# dynalo.net
KiCad netlist of a schematic drawn in EAGLE
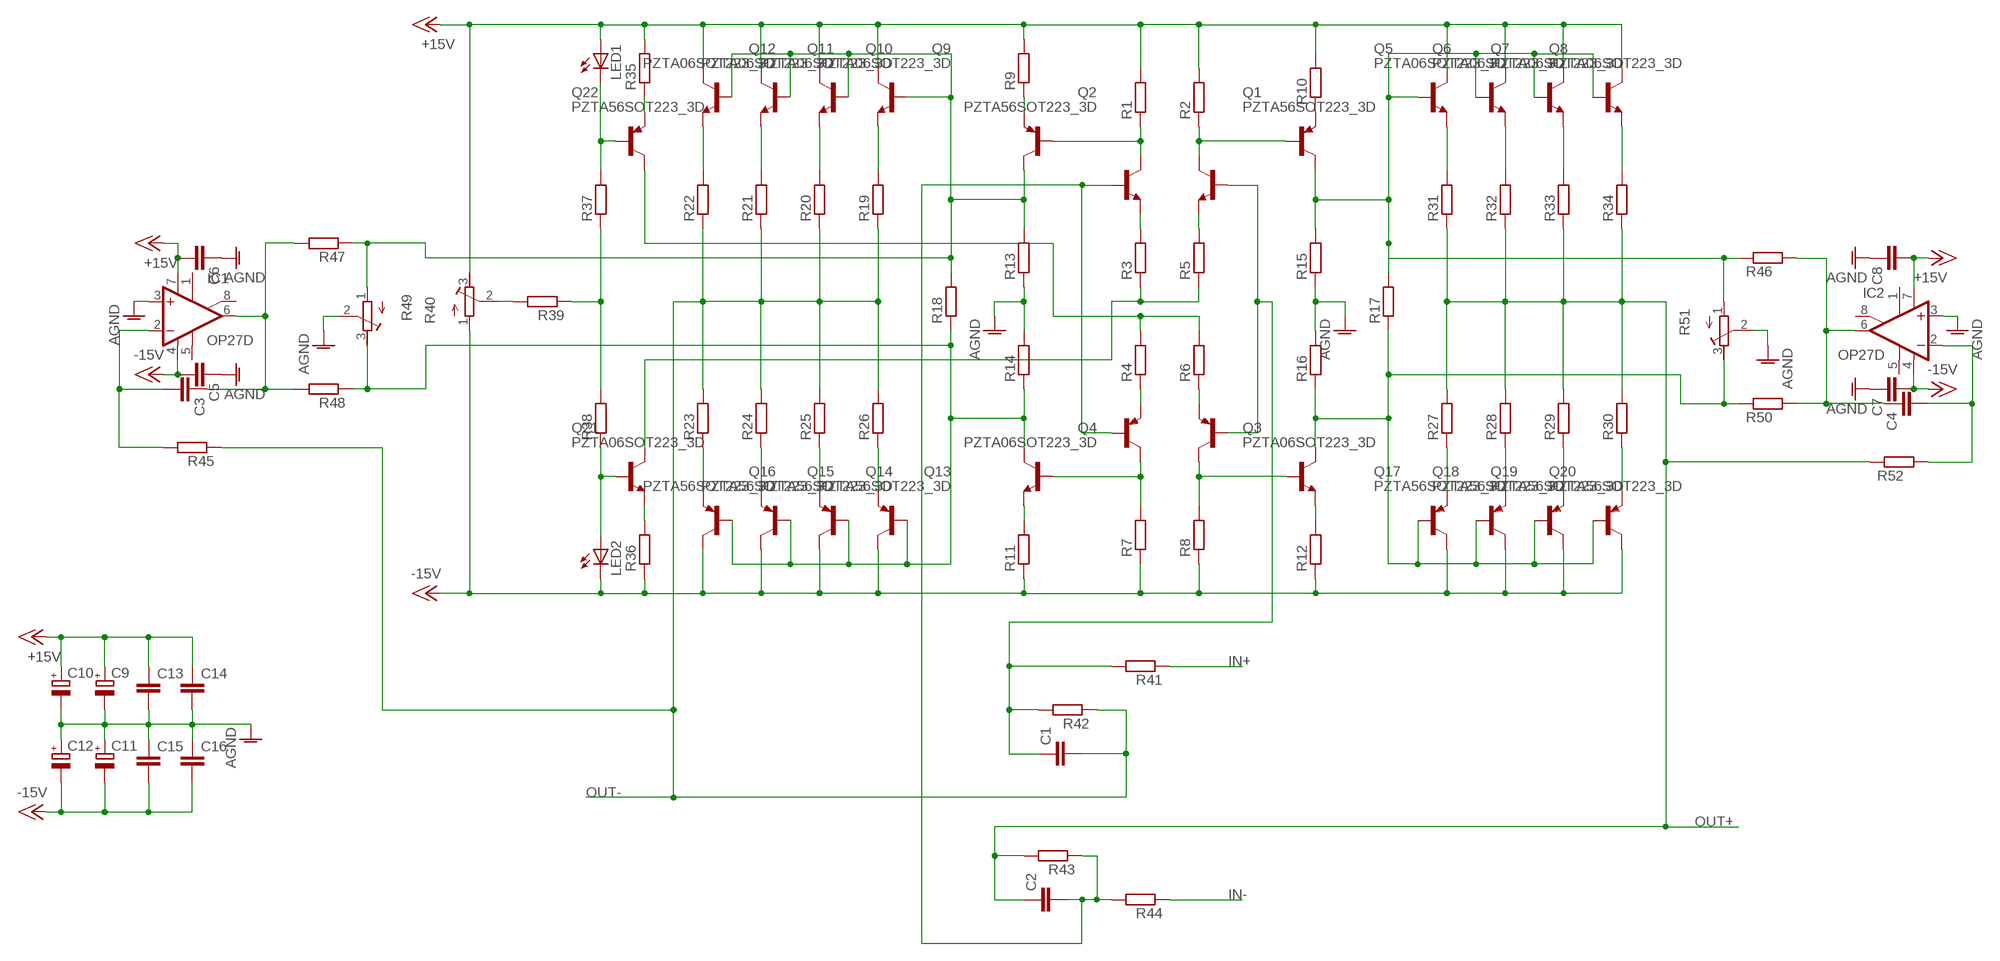
[diagram p0: schematic, sheet 1]

(export (version "E")
  (design (tool "Eeschema 10.0.6"))
  (components
    (comp (ref "C1")
      (value "C-EUC0805K")
      (footprint "eagle-import:C0805K")
      (libsource (lib "eagle-import") (part "C-EUC0805K"))
    )
    (comp (ref "C2")
      (value "C-EUC0805K")
      (footprint "eagle-import:C0805K")
      (libsource (lib "eagle-import") (part "C-EUC0805K"))
    )
    (comp (ref "C3")
      (value "C-EUC0805K")
      (footprint "eagle-import:C0805K")
      (libsource (lib "eagle-import") (part "C-EUC0805K"))
    )
    (comp (ref "C4")
      (value "C-EUC0805K")
      (footprint "eagle-import:C0805K")
      (libsource (lib "eagle-import") (part "C-EUC0805K"))
    )
    (comp (ref "C5")
      (value "C-EUC0805K")
      (footprint "eagle-import:C0805K")
      (libsource (lib "eagle-import") (part "C-EUC0805K"))
    )
    (comp (ref "C6")
      (value "C-EUC0805K")
      (footprint "eagle-import:C0805K")
      (libsource (lib "eagle-import") (part "C-EUC0805K"))
    )
    (comp (ref "C7")
      (value "C-EUC0805K")
      (footprint "eagle-import:C0805K")
      (libsource (lib "eagle-import") (part "C-EUC0805K"))
    )
    (comp (ref "C8")
      (value "C-EUC0805K")
      (footprint "eagle-import:C0805K")
      (libsource (lib "eagle-import") (part "C-EUC0805K"))
    )
    (comp (ref "C9")
      (value "CPOL-EUE5-10.5")
      (footprint "eagle-import:E5-10,5")
      (libsource (lib "eagle-import") (part "CPOL-EUE5-10.5"))
    )
    (comp (ref "C10")
      (value "CPOL-EUE5-10.5")
      (footprint "eagle-import:E5-10,5")
      (libsource (lib "eagle-import") (part "CPOL-EUE5-10.5"))
    )
    (comp (ref "C11")
      (value "CPOL-EUE5-10.5")
      (footprint "eagle-import:E5-10,5")
      (libsource (lib "eagle-import") (part "CPOL-EUE5-10.5"))
    )
    (comp (ref "C12")
      (value "CPOL-EUE5-10.5")
      (footprint "eagle-import:E5-10,5")
      (libsource (lib "eagle-import") (part "CPOL-EUE5-10.5"))
    )
    (comp (ref "C13")
      (value "C-EU050-035X075")
      (footprint "eagle-import:C050-035X075")
      (libsource (lib "eagle-import") (part "C-EU050-035X075"))
    )
    (comp (ref "C14")
      (value "C-EU050-035X075")
      (footprint "eagle-import:C050-035X075")
      (libsource (lib "eagle-import") (part "C-EU050-035X075"))
    )
    (comp (ref "C15")
      (value "C-EU050-035X075")
      (footprint "eagle-import:C050-035X075")
      (libsource (lib "eagle-import") (part "C-EU050-035X075"))
    )
    (comp (ref "C16")
      (value "C-EU050-035X075")
      (footprint "eagle-import:C050-035X075")
      (libsource (lib "eagle-import") (part "C-EU050-035X075"))
    )
    (comp (ref "IC1")
      (value "OP27D")
      (footprint "eagle-import:SO08")
      (libsource (lib "eagle-import") (part "OP27D"))
    )
    (comp (ref "IC2")
      (value "OP27D")
      (footprint "eagle-import:SO08")
      (libsource (lib "eagle-import") (part "OP27D"))
    )
    (comp (ref "LED1")
      (value "LED5MM")
      (footprint "eagle-import:LED5MM")
      (libsource (lib "eagle-import") (part "LED5MM"))
    )
    (comp (ref "LED2")
      (value "LED5MM")
      (footprint "eagle-import:LED5MM")
      (libsource (lib "eagle-import") (part "LED5MM"))
    )
    (comp (ref "Q1")
      (value "PZTA56SOT223_3D")
      (footprint "eagle-import:SOT230P700X180-4")
      (libsource (lib "eagle-import") (part "PZTA56SOT223_3D"))
    )
    (comp (ref "Q2")
      (value "PZTA56SOT223_3D")
      (footprint "eagle-import:SOT230P700X180-4")
      (libsource (lib "eagle-import") (part "PZTA56SOT223_3D"))
    )
    (comp (ref "Q3")
      (value "PZTA06SOT223_3D")
      (footprint "eagle-import:SOT230P700X180-4")
      (libsource (lib "eagle-import") (part "PZTA06SOT223_3D"))
    )
    (comp (ref "Q4")
      (value "PZTA06SOT223_3D")
      (footprint "eagle-import:SOT230P700X180-4")
      (libsource (lib "eagle-import") (part "PZTA06SOT223_3D"))
    )
    (comp (ref "Q5")
      (value "PZTA06SOT223_3D")
      (footprint "eagle-import:SOT230P700X180-4")
      (libsource (lib "eagle-import") (part "PZTA06SOT223_3D"))
    )
    (comp (ref "Q6")
      (value "PZTA06SOT223_3D")
      (footprint "eagle-import:SOT230P700X180-4")
      (libsource (lib "eagle-import") (part "PZTA06SOT223_3D"))
    )
    (comp (ref "Q7")
      (value "PZTA06SOT223_3D")
      (footprint "eagle-import:SOT230P700X180-4")
      (libsource (lib "eagle-import") (part "PZTA06SOT223_3D"))
    )
    (comp (ref "Q8")
      (value "PZTA06SOT223_3D")
      (footprint "eagle-import:SOT230P700X180-4")
      (libsource (lib "eagle-import") (part "PZTA06SOT223_3D"))
    )
    (comp (ref "Q9")
      (value "PZTA06SOT223_3D")
      (footprint "eagle-import:SOT230P700X180-4")
      (libsource (lib "eagle-import") (part "PZTA06SOT223_3D"))
    )
    (comp (ref "Q10")
      (value "PZTA06SOT223_3D")
      (footprint "eagle-import:SOT230P700X180-4")
      (libsource (lib "eagle-import") (part "PZTA06SOT223_3D"))
    )
    (comp (ref "Q11")
      (value "PZTA06SOT223_3D")
      (footprint "eagle-import:SOT230P700X180-4")
      (libsource (lib "eagle-import") (part "PZTA06SOT223_3D"))
    )
    (comp (ref "Q12")
      (value "PZTA06SOT223_3D")
      (footprint "eagle-import:SOT230P700X180-4")
      (libsource (lib "eagle-import") (part "PZTA06SOT223_3D"))
    )
    (comp (ref "Q13")
      (value "PZTA56SOT223_3D")
      (footprint "eagle-import:SOT230P700X180-4")
      (libsource (lib "eagle-import") (part "PZTA56SOT223_3D"))
    )
    (comp (ref "Q14")
      (value "PZTA56SOT223_3D")
      (footprint "eagle-import:SOT230P700X180-4")
      (libsource (lib "eagle-import") (part "PZTA56SOT223_3D"))
    )
    (comp (ref "Q15")
      (value "PZTA56SOT223_3D")
      (footprint "eagle-import:SOT230P700X180-4")
      (libsource (lib "eagle-import") (part "PZTA56SOT223_3D"))
    )
    (comp (ref "Q16")
      (value "PZTA56SOT223_3D")
      (footprint "eagle-import:SOT230P700X180-4")
      (libsource (lib "eagle-import") (part "PZTA56SOT223_3D"))
    )
    (comp (ref "Q17")
      (value "PZTA56SOT223_3D")
      (footprint "eagle-import:SOT230P700X180-4")
      (libsource (lib "eagle-import") (part "PZTA56SOT223_3D"))
    )
    (comp (ref "Q18")
      (value "PZTA56SOT223_3D")
      (footprint "eagle-import:SOT230P700X180-4")
      (libsource (lib "eagle-import") (part "PZTA56SOT223_3D"))
    )
    (comp (ref "Q19")
      (value "PZTA56SOT223_3D")
      (footprint "eagle-import:SOT230P700X180-4")
      (libsource (lib "eagle-import") (part "PZTA56SOT223_3D"))
    )
    (comp (ref "Q20")
      (value "PZTA56SOT223_3D")
      (footprint "eagle-import:SOT230P700X180-4")
      (libsource (lib "eagle-import") (part "PZTA56SOT223_3D"))
    )
    (comp (ref "Q21")
      (value "PZTA06SOT223_3D")
      (footprint "eagle-import:SOT230P700X180-4")
      (libsource (lib "eagle-import") (part "PZTA06SOT223_3D"))
    )
    (comp (ref "Q22")
      (value "PZTA56SOT223_3D")
      (footprint "eagle-import:SOT230P700X180-4")
      (libsource (lib "eagle-import") (part "PZTA56SOT223_3D"))
    )
    (comp (ref "R1")
      (value "R-EU_MMA0204")
      (footprint "eagle-import:RESMELF3413")
      (libsource (lib "eagle-import") (part "R-EU_MMA0204"))
    )
    (comp (ref "R2")
      (value "R-EU_MMA0204")
      (footprint "eagle-import:RESMELF3413")
      (libsource (lib "eagle-import") (part "R-EU_MMA0204"))
    )
    (comp (ref "R3")
      (value "R-EU_MMA0204")
      (footprint "eagle-import:RESMELF3413")
      (libsource (lib "eagle-import") (part "R-EU_MMA0204"))
    )
    (comp (ref "R4")
      (value "R-EU_MMA0204")
      (footprint "eagle-import:RESMELF3413")
      (libsource (lib "eagle-import") (part "R-EU_MMA0204"))
    )
    (comp (ref "R5")
      (value "R-EU_MMA0204")
      (footprint "eagle-import:RESMELF3413")
      (libsource (lib "eagle-import") (part "R-EU_MMA0204"))
    )
    (comp (ref "R6")
      (value "R-EU_MMA0204")
      (footprint "eagle-import:RESMELF3413")
      (libsource (lib "eagle-import") (part "R-EU_MMA0204"))
    )
    (comp (ref "R7")
      (value "R-EU_MMA0204")
      (footprint "eagle-import:RESMELF3413")
      (libsource (lib "eagle-import") (part "R-EU_MMA0204"))
    )
    (comp (ref "R8")
      (value "R-EU_MMA0204")
      (footprint "eagle-import:RESMELF3413")
      (libsource (lib "eagle-import") (part "R-EU_MMA0204"))
    )
    (comp (ref "R9")
      (value "R-EU_MMA0204")
      (footprint "eagle-import:RESMELF3413")
      (libsource (lib "eagle-import") (part "R-EU_MMA0204"))
    )
    (comp (ref "R10")
      (value "R-EU_MMA0204")
      (footprint "eagle-import:RESMELF3413")
      (libsource (lib "eagle-import") (part "R-EU_MMA0204"))
    )
    (comp (ref "R11")
      (value "R-EU_MMA0204")
      (footprint "eagle-import:RESMELF3413")
      (libsource (lib "eagle-import") (part "R-EU_MMA0204"))
    )
    (comp (ref "R12")
      (value "R-EU_MMA0204")
      (footprint "eagle-import:RESMELF3413")
      (libsource (lib "eagle-import") (part "R-EU_MMA0204"))
    )
    (comp (ref "R13")
      (value "R-EU_MMA0204")
      (footprint "eagle-import:RESMELF3413")
      (libsource (lib "eagle-import") (part "R-EU_MMA0204"))
    )
    (comp (ref "R14")
      (value "R-EU_MMA0204")
      (footprint "eagle-import:RESMELF3413")
      (libsource (lib "eagle-import") (part "R-EU_MMA0204"))
    )
    (comp (ref "R15")
      (value "R-EU_MMA0204")
      (footprint "eagle-import:RESMELF3413")
      (libsource (lib "eagle-import") (part "R-EU_MMA0204"))
    )
    (comp (ref "R16")
      (value "R-EU_MMA0204")
      (footprint "eagle-import:RESMELF3413")
      (libsource (lib "eagle-import") (part "R-EU_MMA0204"))
    )
    (comp (ref "R17")
      (value "R-EU_MMA0204")
      (footprint "eagle-import:RESMELF3413")
      (libsource (lib "eagle-import") (part "R-EU_MMA0204"))
    )
    (comp (ref "R18")
      (value "R-EU_MMA0204")
      (footprint "eagle-import:RESMELF3413")
      (libsource (lib "eagle-import") (part "R-EU_MMA0204"))
    )
    (comp (ref "R19")
      (value "R-EU_MMA0204")
      (footprint "eagle-import:RESMELF3413")
      (libsource (lib "eagle-import") (part "R-EU_MMA0204"))
    )
    (comp (ref "R20")
      (value "R-EU_MMA0204")
      (footprint "eagle-import:RESMELF3413")
      (libsource (lib "eagle-import") (part "R-EU_MMA0204"))
    )
    (comp (ref "R21")
      (value "R-EU_MMA0204")
      (footprint "eagle-import:RESMELF3413")
      (libsource (lib "eagle-import") (part "R-EU_MMA0204"))
    )
    (comp (ref "R22")
      (value "R-EU_MMA0204")
      (footprint "eagle-import:RESMELF3413")
      (libsource (lib "eagle-import") (part "R-EU_MMA0204"))
    )
    (comp (ref "R23")
      (value "R-EU_MMA0204")
      (footprint "eagle-import:RESMELF3413")
      (libsource (lib "eagle-import") (part "R-EU_MMA0204"))
    )
    (comp (ref "R24")
      (value "R-EU_MMA0204")
      (footprint "eagle-import:RESMELF3413")
      (libsource (lib "eagle-import") (part "R-EU_MMA0204"))
    )
    (comp (ref "R25")
      (value "R-EU_MMA0204")
      (footprint "eagle-import:RESMELF3413")
      (libsource (lib "eagle-import") (part "R-EU_MMA0204"))
    )
    (comp (ref "R26")
      (value "R-EU_MMA0204")
      (footprint "eagle-import:RESMELF3413")
      (libsource (lib "eagle-import") (part "R-EU_MMA0204"))
    )
    (comp (ref "R27")
      (value "R-EU_MMA0204")
      (footprint "eagle-import:RESMELF3413")
      (libsource (lib "eagle-import") (part "R-EU_MMA0204"))
    )
    (comp (ref "R28")
      (value "R-EU_MMA0204")
      (footprint "eagle-import:RESMELF3413")
      (libsource (lib "eagle-import") (part "R-EU_MMA0204"))
    )
    (comp (ref "R29")
      (value "R-EU_MMA0204")
      (footprint "eagle-import:RESMELF3413")
      (libsource (lib "eagle-import") (part "R-EU_MMA0204"))
    )
    (comp (ref "R30")
      (value "R-EU_MMA0204")
      (footprint "eagle-import:RESMELF3413")
      (libsource (lib "eagle-import") (part "R-EU_MMA0204"))
    )
    (comp (ref "R31")
      (value "R-EU_MMA0204")
      (footprint "eagle-import:RESMELF3413")
      (libsource (lib "eagle-import") (part "R-EU_MMA0204"))
    )
    (comp (ref "R32")
      (value "R-EU_MMA0204")
      (footprint "eagle-import:RESMELF3413")
      (libsource (lib "eagle-import") (part "R-EU_MMA0204"))
    )
    (comp (ref "R33")
      (value "R-EU_MMA0204")
      (footprint "eagle-import:RESMELF3413")
      (libsource (lib "eagle-import") (part "R-EU_MMA0204"))
    )
    (comp (ref "R34")
      (value "R-EU_MMA0204")
      (footprint "eagle-import:RESMELF3413")
      (libsource (lib "eagle-import") (part "R-EU_MMA0204"))
    )
    (comp (ref "R35")
      (value "R-EU_MMA0204")
      (footprint "eagle-import:RESMELF3413")
      (libsource (lib "eagle-import") (part "R-EU_MMA0204"))
    )
    (comp (ref "R36")
      (value "R-EU_MMA0204")
      (footprint "eagle-import:RESMELF3413")
      (libsource (lib "eagle-import") (part "R-EU_MMA0204"))
    )
    (comp (ref "R37")
      (value "R-EU_MMA0204")
      (footprint "eagle-import:RESMELF3413")
      (libsource (lib "eagle-import") (part "R-EU_MMA0204"))
    )
    (comp (ref "R38")
      (value "R-EU_MMA0204")
      (footprint "eagle-import:RESMELF3413")
      (libsource (lib "eagle-import") (part "R-EU_MMA0204"))
    )
    (comp (ref "R39")
      (value "R-EU_MELF0204W")
      (footprint "eagle-import:MINI_MELF-0204W")
      (libsource (lib "eagle-import") (part "R-EU_MELF0204W"))
    )
    (comp (ref "R40")
      (value "R-TRIMM3296W")
      (footprint "eagle-import:RTRIM3296W")
      (libsource (lib "eagle-import") (part "R-TRIMM3296W"))
    )
    (comp (ref "R41")
      (value "R-EU_MMA0204")
      (footprint "eagle-import:RESMELF3413")
      (libsource (lib "eagle-import") (part "R-EU_MMA0204"))
    )
    (comp (ref "R42")
      (value "R-EU_MMA0204")
      (footprint "eagle-import:RESMELF3413")
      (libsource (lib "eagle-import") (part "R-EU_MMA0204"))
    )
    (comp (ref "R43")
      (value "R-EU_MMA0204")
      (footprint "eagle-import:RESMELF3413")
      (libsource (lib "eagle-import") (part "R-EU_MMA0204"))
    )
    (comp (ref "R44")
      (value "R-EU_MMA0204")
      (footprint "eagle-import:RESMELF3413")
      (libsource (lib "eagle-import") (part "R-EU_MMA0204"))
    )
    (comp (ref "R45")
      (value "R-EU_MMA0204")
      (footprint "eagle-import:RESMELF3413")
      (libsource (lib "eagle-import") (part "R-EU_MMA0204"))
    )
    (comp (ref "R46")
      (value "R-EU_MMA0204")
      (footprint "eagle-import:RESMELF3413")
      (libsource (lib "eagle-import") (part "R-EU_MMA0204"))
    )
    (comp (ref "R47")
      (value "R-EU_MMA0204")
      (footprint "eagle-import:RESMELF3413")
      (libsource (lib "eagle-import") (part "R-EU_MMA0204"))
    )
    (comp (ref "R48")
      (value "R-EU_MMA0204")
      (footprint "eagle-import:RESMELF3413")
      (libsource (lib "eagle-import") (part "R-EU_MMA0204"))
    )
    (comp (ref "R49")
      (value "R-TRIMM3296W")
      (footprint "eagle-import:RTRIM3296W")
      (libsource (lib "eagle-import") (part "R-TRIMM3296W"))
    )
    (comp (ref "R50")
      (value "R-EU_MMA0204")
      (footprint "eagle-import:RESMELF3413")
      (libsource (lib "eagle-import") (part "R-EU_MMA0204"))
    )
    (comp (ref "R51")
      (value "R-TRIMM3296W")
      (footprint "eagle-import:RTRIM3296W")
      (libsource (lib "eagle-import") (part "R-TRIMM3296W"))
    )
    (comp (ref "R52")
      (value "R-EU_MMA0204")
      (footprint "eagle-import:RESMELF3413")
      (libsource (lib "eagle-import") (part "R-EU_MMA0204"))
    )
    (comp (ref "U$1")
      (value "TRANSISTOR-ARRAYS_THAT340THAT3403D")
      (footprint "eagle-import:DIP762W53P254L1969H508Q14A")
      (libsource (lib "eagle-import") (part "TRANSISTOR-ARRAYS_THAT340THAT3403D"))
    )
  )
  (nets
    (net (code "1") (name "+15V") (class "Default")
      (node (ref "C10") (pin "+") (pinfunction "+_+") (pintype "passive"))
      (node (ref "C13") (pin "1") (pinfunction "1_1") (pintype "passive"))
      (node (ref "C14") (pin "1") (pinfunction "1_1") (pintype "passive"))
      (node (ref "C6") (pin "2") (pinfunction "2_2") (pintype "passive"))
      (node (ref "C8") (pin "2") (pinfunction "2_2") (pintype "passive"))
      (node (ref "C9") (pin "+") (pinfunction "+_+") (pintype "passive"))
      (node (ref "IC1") (pin "7") (pinfunction "V+_7") (pintype "power_in"))
      (node (ref "IC2") (pin "7") (pinfunction "V+_7") (pintype "power_in"))
      (node (ref "LED1") (pin "A") (pinfunction "A_A") (pintype "passive"))
      (node (ref "Q10") (pin "2") (pinfunction "C_2") (pintype "passive"))
      (node (ref "Q10") (pin "4") (pinfunction "C_4") (pintype "passive"))
      (node (ref "Q11") (pin "2") (pinfunction "C_2") (pintype "passive"))
      (node (ref "Q11") (pin "4") (pinfunction "C_4") (pintype "passive"))
      (node (ref "Q12") (pin "2") (pinfunction "C_2") (pintype "passive"))
      (node (ref "Q12") (pin "4") (pinfunction "C_4") (pintype "passive"))
      (node (ref "Q5") (pin "2") (pinfunction "C_2") (pintype "passive"))
      (node (ref "Q5") (pin "4") (pinfunction "C_4") (pintype "passive"))
      (node (ref "Q6") (pin "2") (pinfunction "C_2") (pintype "passive"))
      (node (ref "Q6") (pin "4") (pinfunction "C_4") (pintype "passive"))
      (node (ref "Q7") (pin "2") (pinfunction "C_2") (pintype "passive"))
      (node (ref "Q7") (pin "4") (pinfunction "C_4") (pintype "passive"))
      (node (ref "Q8") (pin "2") (pinfunction "C_2") (pintype "passive"))
      (node (ref "Q8") (pin "4") (pinfunction "C_4") (pintype "passive"))
      (node (ref "Q9") (pin "2") (pinfunction "C_2") (pintype "passive"))
      (node (ref "Q9") (pin "4") (pinfunction "C_4") (pintype "passive"))
      (node (ref "R1") (pin "2") (pinfunction "2_2") (pintype "passive"))
      (node (ref "R10") (pin "2") (pinfunction "2_2") (pintype "passive"))
      (node (ref "R2") (pin "2") (pinfunction "2_2") (pintype "passive"))
      (node (ref "R35") (pin "2") (pinfunction "2_2") (pintype "passive"))
      (node (ref "R40") (pin "3") (pinfunction "E_3") (pintype "passive"))
      (node (ref "R9") (pin "2") (pinfunction "2_2") (pintype "passive"))
    )
    (net (code "2") (name "-15V") (class "Default")
      (node (ref "C11") (pin "-") (pinfunction "-_-") (pintype "passive"))
      (node (ref "C12") (pin "-") (pinfunction "-_-") (pintype "passive"))
      (node (ref "C15") (pin "2") (pinfunction "2_2") (pintype "passive"))
      (node (ref "C16") (pin "2") (pinfunction "2_2") (pintype "passive"))
      (node (ref "C5") (pin "2") (pinfunction "2_2") (pintype "passive"))
      (node (ref "C7") (pin "2") (pinfunction "2_2") (pintype "passive"))
      (node (ref "IC1") (pin "4") (pinfunction "V-_4") (pintype "power_in"))
      (node (ref "IC2") (pin "4") (pinfunction "V-_4") (pintype "power_in"))
      (node (ref "LED2") (pin "K") (pinfunction "C_K") (pintype "passive"))
      (node (ref "Q13") (pin "2") (pinfunction "C_2") (pintype "passive"))
      (node (ref "Q13") (pin "4") (pinfunction "C_4") (pintype "passive"))
      (node (ref "Q14") (pin "2") (pinfunction "C_2") (pintype "passive"))
      (node (ref "Q14") (pin "4") (pinfunction "C_4") (pintype "passive"))
      (node (ref "Q15") (pin "2") (pinfunction "C_2") (pintype "passive"))
      (node (ref "Q15") (pin "4") (pinfunction "C_4") (pintype "passive"))
      (node (ref "Q16") (pin "2") (pinfunction "C_2") (pintype "passive"))
      (node (ref "Q16") (pin "4") (pinfunction "C_4") (pintype "passive"))
      (node (ref "Q17") (pin "2") (pinfunction "C_2") (pintype "passive"))
      (node (ref "Q17") (pin "4") (pinfunction "C_4") (pintype "passive"))
      (node (ref "Q18") (pin "2") (pinfunction "C_2") (pintype "passive"))
      (node (ref "Q18") (pin "4") (pinfunction "C_4") (pintype "passive"))
      (node (ref "Q19") (pin "2") (pinfunction "C_2") (pintype "passive"))
      (node (ref "Q19") (pin "4") (pinfunction "C_4") (pintype "passive"))
      (node (ref "Q20") (pin "2") (pinfunction "C_2") (pintype "passive"))
      (node (ref "Q20") (pin "4") (pinfunction "C_4") (pintype "passive"))
      (node (ref "R11") (pin "1") (pinfunction "1_1") (pintype "passive"))
      (node (ref "R12") (pin "1") (pinfunction "1_1") (pintype "passive"))
      (node (ref "R36") (pin "1") (pinfunction "1_1") (pintype "passive"))
      (node (ref "R40") (pin "1") (pinfunction "A_1") (pintype "passive"))
      (node (ref "R7") (pin "1") (pinfunction "1_1") (pintype "passive"))
      (node (ref "R8") (pin "1") (pinfunction "1_1") (pintype "passive"))
    )
    (net (code "3") (name "/IN+") (class "Default")
      (node (ref "R41") (pin "1") (pinfunction "1_1") (pintype "passive"))
    )
    (net (code "4") (name "/IN-") (class "Default")
      (node (ref "R44") (pin "1") (pinfunction "1_1") (pintype "passive"))
    )
    (net (code "5") (name "/OUT+") (class "Default")
      (node (ref "C2") (pin "1") (pinfunction "1_1") (pintype "passive"))
      (node (ref "R27") (pin "2") (pinfunction "2_2") (pintype "passive"))
      (node (ref "R28") (pin "2") (pinfunction "2_2") (pintype "passive"))
      (node (ref "R29") (pin "2") (pinfunction "2_2") (pintype "passive"))
      (node (ref "R30") (pin "2") (pinfunction "2_2") (pintype "passive"))
      (node (ref "R31") (pin "1") (pinfunction "1_1") (pintype "passive"))
      (node (ref "R32") (pin "1") (pinfunction "1_1") (pintype "passive"))
      (node (ref "R33") (pin "1") (pinfunction "1_1") (pintype "passive"))
      (node (ref "R34") (pin "1") (pinfunction "1_1") (pintype "passive"))
      (node (ref "R43") (pin "2") (pinfunction "2_2") (pintype "passive"))
      (node (ref "R52") (pin "1") (pinfunction "1_1") (pintype "passive"))
    )
    (net (code "6") (name "/OUT-") (class "Default")
      (node (ref "C1") (pin "2") (pinfunction "2_2") (pintype "passive"))
      (node (ref "R19") (pin "1") (pinfunction "1_1") (pintype "passive"))
      (node (ref "R20") (pin "1") (pinfunction "1_1") (pintype "passive"))
      (node (ref "R21") (pin "1") (pinfunction "1_1") (pintype "passive"))
      (node (ref "R22") (pin "1") (pinfunction "1_1") (pintype "passive"))
      (node (ref "R23") (pin "2") (pinfunction "2_2") (pintype "passive"))
      (node (ref "R24") (pin "2") (pinfunction "2_2") (pintype "passive"))
      (node (ref "R25") (pin "2") (pinfunction "2_2") (pintype "passive"))
      (node (ref "R26") (pin "2") (pinfunction "2_2") (pintype "passive"))
      (node (ref "R42") (pin "1") (pinfunction "1_1") (pintype "passive"))
      (node (ref "R45") (pin "1") (pinfunction "1_1") (pintype "passive"))
    )
    (net (code "7") (name "AGND") (class "Default")
      (node (ref "C10") (pin "-") (pinfunction "-_-") (pintype "passive"))
      (node (ref "C11") (pin "+") (pinfunction "+_+") (pintype "passive"))
      (node (ref "C12") (pin "+") (pinfunction "+_+") (pintype "passive"))
      (node (ref "C13") (pin "2") (pinfunction "2_2") (pintype "passive"))
      (node (ref "C14") (pin "2") (pinfunction "2_2") (pintype "passive"))
      (node (ref "C15") (pin "1") (pinfunction "1_1") (pintype "passive"))
      (node (ref "C16") (pin "1") (pinfunction "1_1") (pintype "passive"))
      (node (ref "C5") (pin "1") (pinfunction "1_1") (pintype "passive"))
      (node (ref "C6") (pin "1") (pinfunction "1_1") (pintype "passive"))
      (node (ref "C7") (pin "1") (pinfunction "1_1") (pintype "passive"))
      (node (ref "C8") (pin "1") (pinfunction "1_1") (pintype "passive"))
      (node (ref "C9") (pin "-") (pinfunction "-_-") (pintype "passive"))
      (node (ref "IC1") (pin "3") (pinfunction "+IN_3") (pintype "input"))
      (node (ref "IC2") (pin "3") (pinfunction "+IN_3") (pintype "input"))
      (node (ref "R13") (pin "1") (pinfunction "1_1") (pintype "passive"))
      (node (ref "R14") (pin "2") (pinfunction "2_2") (pintype "passive"))
      (node (ref "R15") (pin "1") (pinfunction "1_1") (pintype "passive"))
      (node (ref "R16") (pin "2") (pinfunction "2_2") (pintype "passive"))
      (node (ref "R49") (pin "2") (pinfunction "S_2") (pintype "passive"))
      (node (ref "R51") (pin "2") (pinfunction "S_2") (pintype "passive"))
    )
    (net (code "8") (name "Net-(IC1--IN)") (class "Default")
      (node (ref "C3") (pin "2") (pinfunction "2_2") (pintype "passive"))
      (node (ref "IC1") (pin "2") (pinfunction "-IN_2") (pintype "input"))
      (node (ref "R45") (pin "2") (pinfunction "2_2") (pintype "passive"))
    )
    (net (code "9") (name "Net-(IC1-OUT)") (class "Default")
      (node (ref "C3") (pin "1") (pinfunction "1_1") (pintype "passive"))
      (node (ref "IC1") (pin "6") (pinfunction "OUT_6") (pintype "output"))
      (node (ref "R47") (pin "2") (pinfunction "2_2") (pintype "passive"))
      (node (ref "R48") (pin "2") (pinfunction "2_2") (pintype "passive"))
    )
    (net (code "10") (name "Net-(IC2--IN)") (class "Default")
      (node (ref "C4") (pin "2") (pinfunction "2_2") (pintype "passive"))
      (node (ref "IC2") (pin "2") (pinfunction "-IN_2") (pintype "input"))
      (node (ref "R52") (pin "2") (pinfunction "2_2") (pintype "passive"))
    )
    (net (code "11") (name "Net-(IC2-OUT)") (class "Default")
      (node (ref "C4") (pin "1") (pinfunction "1_1") (pintype "passive"))
      (node (ref "IC2") (pin "6") (pinfunction "OUT_6") (pintype "output"))
      (node (ref "R46") (pin "2") (pinfunction "2_2") (pintype "passive"))
      (node (ref "R50") (pin "2") (pinfunction "2_2") (pintype "passive"))
    )
    (net (code "12") (name "Net-(LED1-C)") (class "Default")
      (node (ref "LED1") (pin "K") (pinfunction "C_K") (pintype "passive"))
      (node (ref "Q22") (pin "1") (pinfunction "B_1") (pintype "passive"))
      (node (ref "R37") (pin "2") (pinfunction "2_2") (pintype "passive"))
    )
    (net (code "13") (name "Net-(Q1-B)") (class "Default")
      (node (ref "Q1") (pin "1") (pinfunction "B_1") (pintype "passive"))
      (node (ref "R2") (pin "1") (pinfunction "1_1") (pintype "passive"))
      (node (ref "U$1") (pin "1") (pinfunction "C_1") (pintype "passive"))
    )
    (net (code "14") (name "Net-(Q1-E)") (class "Default")
      (node (ref "Q1") (pin "3") (pinfunction "E_3") (pintype "passive"))
      (node (ref "R10") (pin "1") (pinfunction "1_1") (pintype "passive"))
    )
    (net (code "15") (name "Net-(Q2-B)") (class "Default")
      (node (ref "Q2") (pin "1") (pinfunction "B_1") (pintype "passive"))
      (node (ref "R1") (pin "1") (pinfunction "1_1") (pintype "passive"))
      (node (ref "U$1") (pin "14") (pinfunction "C_14") (pintype "passive"))
    )
    (net (code "16") (name "Net-(Q2-E)") (class "Default")
      (node (ref "Q2") (pin "3") (pinfunction "E_3") (pintype "passive"))
      (node (ref "R9") (pin "1") (pinfunction "1_1") (pintype "passive"))
    )
    (net (code "17") (name "Net-(Q3-B)") (class "Default")
      (node (ref "Q3") (pin "1") (pinfunction "B_1") (pintype "passive"))
      (node (ref "R8") (pin "2") (pinfunction "2_2") (pintype "passive"))
      (node (ref "U$1") (pin "7") (pinfunction "C_7") (pintype "passive"))
    )
    (net (code "18") (name "Net-(Q3-E)") (class "Default")
      (node (ref "Q3") (pin "3") (pinfunction "E_3") (pintype "passive"))
      (node (ref "R12") (pin "2") (pinfunction "2_2") (pintype "passive"))
    )
    (net (code "19") (name "Net-(Q4-B)") (class "Default")
      (node (ref "Q4") (pin "1") (pinfunction "B_1") (pintype "passive"))
      (node (ref "R7") (pin "2") (pinfunction "2_2") (pintype "passive"))
      (node (ref "U$1") (pin "8") (pinfunction "C_8") (pintype "passive"))
    )
    (net (code "20") (name "Net-(Q4-E)") (class "Default")
      (node (ref "Q4") (pin "3") (pinfunction "E_3") (pintype "passive"))
      (node (ref "R11") (pin "2") (pinfunction "2_2") (pintype "passive"))
    )
    (net (code "21") (name "Net-(Q5-B)") (class "Default")
      (node (ref "Q1") (pin "2") (pinfunction "C_2") (pintype "passive"))
      (node (ref "Q1") (pin "4") (pinfunction "C_4") (pintype "passive"))
      (node (ref "Q5") (pin "1") (pinfunction "B_1") (pintype "passive"))
      (node (ref "Q6") (pin "1") (pinfunction "B_1") (pintype "passive"))
      (node (ref "Q7") (pin "1") (pinfunction "B_1") (pintype "passive"))
      (node (ref "Q8") (pin "1") (pinfunction "B_1") (pintype "passive"))
      (node (ref "R15") (pin "2") (pinfunction "2_2") (pintype "passive"))
      (node (ref "R17") (pin "2") (pinfunction "2_2") (pintype "passive"))
      (node (ref "R46") (pin "1") (pinfunction "1_1") (pintype "passive"))
      (node (ref "R51") (pin "1") (pinfunction "A_1") (pintype "passive"))
    )
    (net (code "22") (name "Net-(Q5-E)") (class "Default")
      (node (ref "Q5") (pin "3") (pinfunction "E_3") (pintype "passive"))
      (node (ref "R31") (pin "2") (pinfunction "2_2") (pintype "passive"))
    )
    (net (code "23") (name "Net-(Q6-E)") (class "Default")
      (node (ref "Q6") (pin "3") (pinfunction "E_3") (pintype "passive"))
      (node (ref "R32") (pin "2") (pinfunction "2_2") (pintype "passive"))
    )
    (net (code "24") (name "Net-(Q7-E)") (class "Default")
      (node (ref "Q7") (pin "3") (pinfunction "E_3") (pintype "passive"))
      (node (ref "R33") (pin "2") (pinfunction "2_2") (pintype "passive"))
    )
    (net (code "25") (name "Net-(Q8-E)") (class "Default")
      (node (ref "Q8") (pin "3") (pinfunction "E_3") (pintype "passive"))
      (node (ref "R34") (pin "2") (pinfunction "2_2") (pintype "passive"))
    )
    (net (code "26") (name "Net-(Q9-E)") (class "Default")
      (node (ref "Q9") (pin "3") (pinfunction "E_3") (pintype "passive"))
      (node (ref "R19") (pin "2") (pinfunction "2_2") (pintype "passive"))
    )
    (net (code "27") (name "Net-(Q10-B)") (class "Default")
      (node (ref "Q10") (pin "1") (pinfunction "B_1") (pintype "passive"))
      (node (ref "Q11") (pin "1") (pinfunction "B_1") (pintype "passive"))
      (node (ref "Q12") (pin "1") (pinfunction "B_1") (pintype "passive"))
      (node (ref "Q2") (pin "2") (pinfunction "C_2") (pintype "passive"))
      (node (ref "Q2") (pin "4") (pinfunction "C_4") (pintype "passive"))
      (node (ref "Q9") (pin "1") (pinfunction "B_1") (pintype "passive"))
      (node (ref "R13") (pin "2") (pinfunction "2_2") (pintype "passive"))
      (node (ref "R18") (pin "2") (pinfunction "2_2") (pintype "passive"))
      (node (ref "R47") (pin "1") (pinfunction "1_1") (pintype "passive"))
      (node (ref "R49") (pin "1") (pinfunction "A_1") (pintype "passive"))
    )
    (net (code "28") (name "Net-(Q10-E)") (class "Default")
      (node (ref "Q10") (pin "3") (pinfunction "E_3") (pintype "passive"))
      (node (ref "R20") (pin "2") (pinfunction "2_2") (pintype "passive"))
    )
    (net (code "29") (name "Net-(Q11-E)") (class "Default")
      (node (ref "Q11") (pin "3") (pinfunction "E_3") (pintype "passive"))
      (node (ref "R21") (pin "2") (pinfunction "2_2") (pintype "passive"))
    )
    (net (code "30") (name "Net-(Q12-E)") (class "Default")
      (node (ref "Q12") (pin "3") (pinfunction "E_3") (pintype "passive"))
      (node (ref "R22") (pin "2") (pinfunction "2_2") (pintype "passive"))
    )
    (net (code "31") (name "Net-(Q13-B)") (class "Default")
      (node (ref "Q13") (pin "1") (pinfunction "B_1") (pintype "passive"))
      (node (ref "Q14") (pin "1") (pinfunction "B_1") (pintype "passive"))
      (node (ref "Q15") (pin "1") (pinfunction "B_1") (pintype "passive"))
      (node (ref "Q16") (pin "1") (pinfunction "B_1") (pintype "passive"))
      (node (ref "Q4") (pin "2") (pinfunction "C_2") (pintype "passive"))
      (node (ref "Q4") (pin "4") (pinfunction "C_4") (pintype "passive"))
      (node (ref "R14") (pin "1") (pinfunction "1_1") (pintype "passive"))
      (node (ref "R18") (pin "1") (pinfunction "1_1") (pintype "passive"))
      (node (ref "R48") (pin "1") (pinfunction "1_1") (pintype "passive"))
      (node (ref "R49") (pin "3") (pinfunction "E_3") (pintype "passive"))
    )
    (net (code "32") (name "Net-(Q13-E)") (class "Default")
      (node (ref "Q13") (pin "3") (pinfunction "E_3") (pintype "passive"))
      (node (ref "R26") (pin "1") (pinfunction "1_1") (pintype "passive"))
    )
    (net (code "33") (name "Net-(Q14-E)") (class "Default")
      (node (ref "Q14") (pin "3") (pinfunction "E_3") (pintype "passive"))
      (node (ref "R25") (pin "1") (pinfunction "1_1") (pintype "passive"))
    )
    (net (code "34") (name "Net-(Q15-E)") (class "Default")
      (node (ref "Q15") (pin "3") (pinfunction "E_3") (pintype "passive"))
      (node (ref "R24") (pin "1") (pinfunction "1_1") (pintype "passive"))
    )
    (net (code "35") (name "Net-(Q16-E)") (class "Default")
      (node (ref "Q16") (pin "3") (pinfunction "E_3") (pintype "passive"))
      (node (ref "R23") (pin "1") (pinfunction "1_1") (pintype "passive"))
    )
    (net (code "36") (name "Net-(Q17-B)") (class "Default")
      (node (ref "Q17") (pin "1") (pinfunction "B_1") (pintype "passive"))
      (node (ref "Q18") (pin "1") (pinfunction "B_1") (pintype "passive"))
      (node (ref "Q19") (pin "1") (pinfunction "B_1") (pintype "passive"))
      (node (ref "Q20") (pin "1") (pinfunction "B_1") (pintype "passive"))
      (node (ref "Q3") (pin "2") (pinfunction "C_2") (pintype "passive"))
      (node (ref "Q3") (pin "4") (pinfunction "C_4") (pintype "passive"))
      (node (ref "R16") (pin "1") (pinfunction "1_1") (pintype "passive"))
      (node (ref "R17") (pin "1") (pinfunction "1_1") (pintype "passive"))
      (node (ref "R50") (pin "1") (pinfunction "1_1") (pintype "passive"))
      (node (ref "R51") (pin "3") (pinfunction "E_3") (pintype "passive"))
    )
    (net (code "37") (name "Net-(Q17-E)") (class "Default")
      (node (ref "Q17") (pin "3") (pinfunction "E_3") (pintype "passive"))
      (node (ref "R27") (pin "1") (pinfunction "1_1") (pintype "passive"))
    )
    (net (code "38") (name "Net-(Q18-E)") (class "Default")
      (node (ref "Q18") (pin "3") (pinfunction "E_3") (pintype "passive"))
      (node (ref "R28") (pin "1") (pinfunction "1_1") (pintype "passive"))
    )
    (net (code "39") (name "Net-(Q19-E)") (class "Default")
      (node (ref "Q19") (pin "3") (pinfunction "E_3") (pintype "passive"))
      (node (ref "R29") (pin "1") (pinfunction "1_1") (pintype "passive"))
    )
    (net (code "40") (name "Net-(Q20-E)") (class "Default")
      (node (ref "Q20") (pin "3") (pinfunction "E_3") (pintype "passive"))
      (node (ref "R30") (pin "1") (pinfunction "1_1") (pintype "passive"))
    )
    (net (code "41") (name "Net-(Q21-B)") (class "Default")
      (node (ref "LED2") (pin "A") (pinfunction "A_A") (pintype "passive"))
      (node (ref "Q21") (pin "1") (pinfunction "B_1") (pintype "passive"))
      (node (ref "R38") (pin "1") (pinfunction "1_1") (pintype "passive"))
    )
    (net (code "42") (name "Net-(Q21-C-Pad2)") (class "Default")
      (node (ref "Q21") (pin "2") (pinfunction "C_2") (pintype "passive"))
      (node (ref "Q21") (pin "4") (pinfunction "C_4") (pintype "passive"))
      (node (ref "R3") (pin "1") (pinfunction "1_1") (pintype "passive"))
      (node (ref "R5") (pin "1") (pinfunction "1_1") (pintype "passive"))
    )
    (net (code "43") (name "Net-(Q21-E)") (class "Default")
      (node (ref "Q21") (pin "3") (pinfunction "E_3") (pintype "passive"))
      (node (ref "R36") (pin "2") (pinfunction "2_2") (pintype "passive"))
    )
    (net (code "44") (name "Net-(Q22-C-Pad2)") (class "Default")
      (node (ref "Q22") (pin "2") (pinfunction "C_2") (pintype "passive"))
      (node (ref "Q22") (pin "4") (pinfunction "C_4") (pintype "passive"))
      (node (ref "R4") (pin "2") (pinfunction "2_2") (pintype "passive"))
      (node (ref "R6") (pin "2") (pinfunction "2_2") (pintype "passive"))
    )
    (net (code "45") (name "Net-(Q22-E)") (class "Default")
      (node (ref "Q22") (pin "3") (pinfunction "E_3") (pintype "passive"))
      (node (ref "R35") (pin "1") (pinfunction "1_1") (pintype "passive"))
    )
    (net (code "46") (name "Net-(R37-Pad1)") (class "Default")
      (node (ref "R37") (pin "1") (pinfunction "1_1") (pintype "passive"))
      (node (ref "R38") (pin "2") (pinfunction "2_2") (pintype "passive"))
      (node (ref "R39") (pin "1") (pinfunction "1_1") (pintype "passive"))
    )
    (net (code "47") (name "Net-(R40-S)") (class "Default")
      (node (ref "R39") (pin "2") (pinfunction "2_2") (pintype "passive"))
      (node (ref "R40") (pin "2") (pinfunction "S_2") (pintype "passive"))
    )
    (net (code "48") (name "Net-(U$1A-B)") (class "Default")
      (node (ref "C1") (pin "1") (pinfunction "1_1") (pintype "passive"))
      (node (ref "R41") (pin "2") (pinfunction "2_2") (pintype "passive"))
      (node (ref "R42") (pin "2") (pinfunction "2_2") (pintype "passive"))
      (node (ref "U$1") (pin "2") (pinfunction "B_2") (pintype "passive"))
      (node (ref "U$1") (pin "6") (pinfunction "B_6") (pintype "passive"))
    )
    (net (code "49") (name "Net-(U$1A-E)") (class "Default")
      (node (ref "R5") (pin "2") (pinfunction "2_2") (pintype "passive"))
      (node (ref "U$1") (pin "3") (pinfunction "E_3") (pintype "passive"))
    )
    (net (code "50") (name "Net-(U$1B-B)") (class "Default")
      (node (ref "C2") (pin "2") (pinfunction "2_2") (pintype "passive"))
      (node (ref "R43") (pin "1") (pinfunction "1_1") (pintype "passive"))
      (node (ref "R44") (pin "2") (pinfunction "2_2") (pintype "passive"))
      (node (ref "U$1") (pin "13") (pinfunction "B_13") (pintype "passive"))
      (node (ref "U$1") (pin "9") (pinfunction "B_9") (pintype "passive"))
    )
    (net (code "51") (name "Net-(U$1B-E)") (class "Default")
      (node (ref "R3") (pin "2") (pinfunction "2_2") (pintype "passive"))
      (node (ref "U$1") (pin "12") (pinfunction "E_12") (pintype "passive"))
    )
    (net (code "52") (name "Net-(U$1C-E)") (class "Default")
      (node (ref "R6") (pin "1") (pinfunction "1_1") (pintype "passive"))
      (node (ref "U$1") (pin "5") (pinfunction "E_5") (pintype "passive"))
    )
    (net (code "53") (name "Net-(U$1D-E)") (class "Default")
      (node (ref "R4") (pin "1") (pinfunction "1_1") (pintype "passive"))
      (node (ref "U$1") (pin "10") (pinfunction "E_10") (pintype "passive"))
    )
    (net (code "54") (name "unconnected-(IC1-ON1-Pad1)") (class "Default")
      (node (ref "IC1") (pin "1") (pinfunction "ON1_1") (pintype "passive"))
    )
    (net (code "55") (name "unconnected-(IC1-ON2-Pad8)") (class "Default")
      (node (ref "IC1") (pin "8") (pinfunction "ON2_8") (pintype "passive"))
    )
    (net (code "56") (name "unconnected-(IC1-OPT-Pad5)") (class "Default")
      (node (ref "IC1") (pin "5") (pinfunction "OPT_5") (pintype "passive"))
    )
    (net (code "57") (name "unconnected-(IC2-ON1-Pad1)") (class "Default")
      (node (ref "IC2") (pin "1") (pinfunction "ON1_1") (pintype "passive"))
    )
    (net (code "58") (name "unconnected-(IC2-ON2-Pad8)") (class "Default")
      (node (ref "IC2") (pin "8") (pinfunction "ON2_8") (pintype "passive"))
    )
    (net (code "59") (name "unconnected-(IC2-OPT-Pad5)") (class "Default")
      (node (ref "IC2") (pin "5") (pinfunction "OPT_5") (pintype "passive"))
    )
  )
)
